# interface.net
KiCad netlist of a schematic drawn in EAGLE
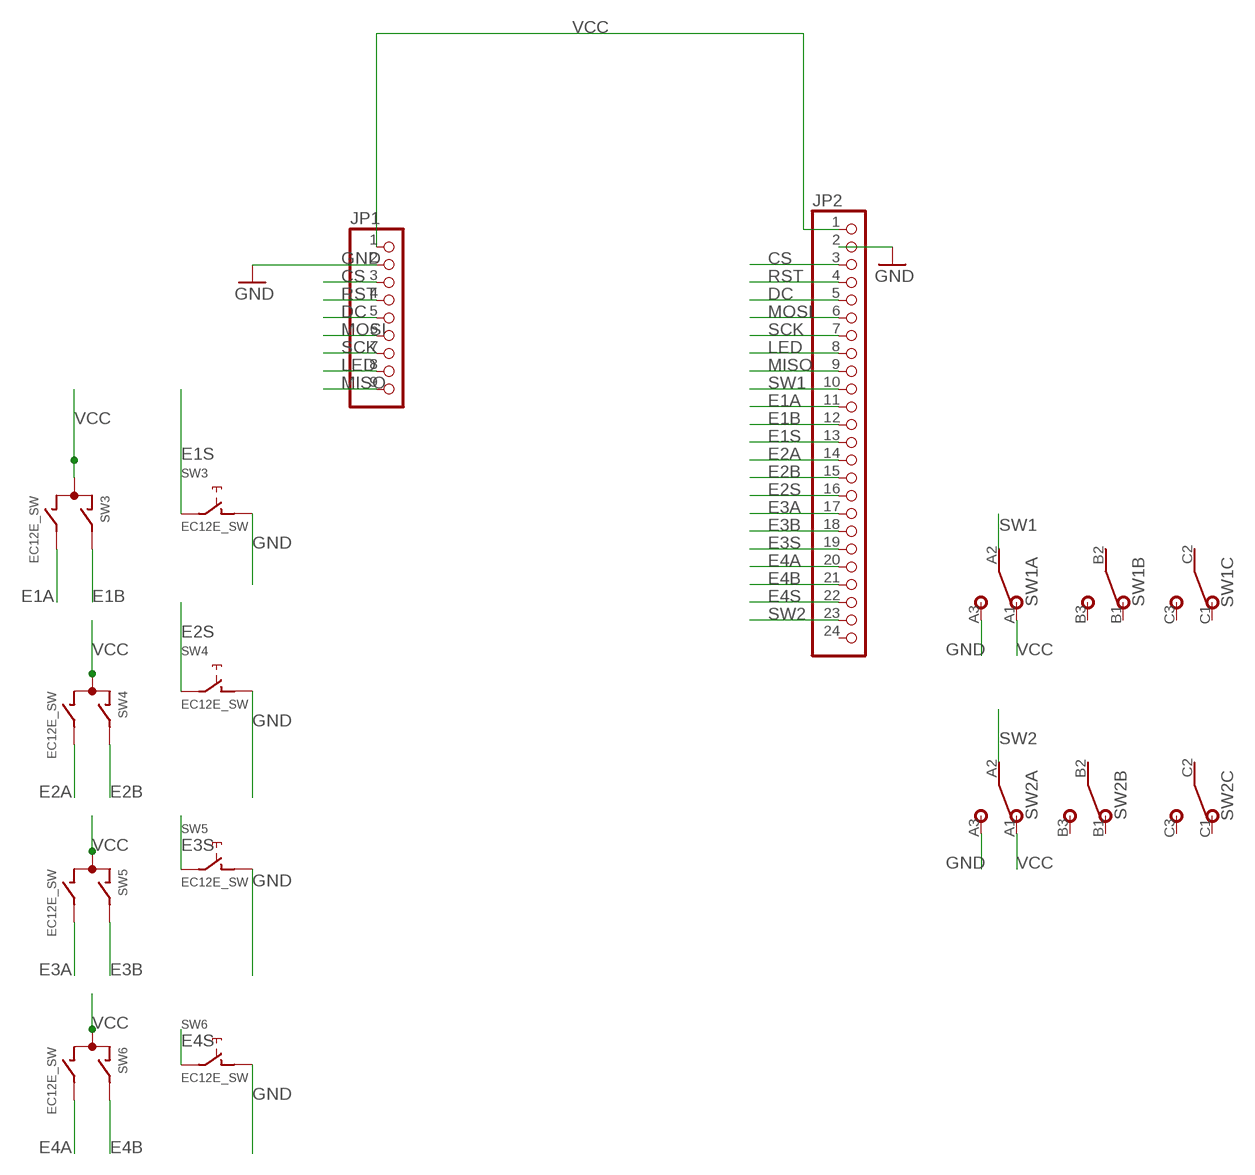
[diagram p0: schematic, sheet 1]

(export (version "E")
  (design (tool "Eeschema 10.0.6"))
  (components
    (comp (ref "JP1")
      (value "PINHD-1X9")
      (footprint "eagle-import:1X09")
      (libsource (lib "eagle-import") (part "PINHD-1X9"))
    )
    (comp (ref "JP2")
      (value "PINHD-1X24")
      (footprint "eagle-import:1X24")
      (libsource (lib "eagle-import") (part "PINHD-1X24"))
    )
    (comp (ref "SW1")
      (value "3PDTBLUE")
      (footprint "eagle-import:CHINABLUE")
      (libsource (lib "eagle-import") (part "3PDTBLUE"))
    )
    (comp (ref "SW2")
      (value "3PDTBLUE")
      (footprint "eagle-import:CHINABLUE")
      (libsource (lib "eagle-import") (part "3PDTBLUE"))
    )
    (comp (ref "SW3")
      (value "EC12E_SW")
      (footprint "eagle-import:ALPS_EC12E_SW")
      (fields (field (name "MPN") "EC12E2424407"))
      (libsource (lib "eagle-import") (part "EC12E_SW"))
    )
    (comp (ref "SW4")
      (value "EC12E_SW")
      (footprint "eagle-import:ALPS_EC12E_SW")
      (fields (field (name "MPN") "EC12E2424407"))
      (libsource (lib "eagle-import") (part "EC12E_SW"))
    )
    (comp (ref "SW5")
      (value "EC12E_SW")
      (footprint "eagle-import:ALPS_EC12E_SW")
      (fields (field (name "MPN") "EC12E2424407"))
      (libsource (lib "eagle-import") (part "EC12E_SW"))
    )
    (comp (ref "SW6")
      (value "EC12E_SW")
      (footprint "eagle-import:ALPS_EC12E_SW")
      (fields (field (name "MPN") "EC12E2424407"))
      (libsource (lib "eagle-import") (part "EC12E_SW"))
    )
  )
  (nets
    (net (code "1") (name "/CS") (class "Default")
      (node (ref "JP1") (pin "3") (pinfunction "3_3") (pintype "passive"))
      (node (ref "JP2") (pin "3") (pinfunction "3_3") (pintype "passive"))
    )
    (net (code "2") (name "/DC") (class "Default")
      (node (ref "JP1") (pin "5") (pinfunction "5_5") (pintype "passive"))
      (node (ref "JP2") (pin "5") (pinfunction "5_5") (pintype "passive"))
    )
    (net (code "3") (name "/E1A") (class "Default")
      (node (ref "JP2") (pin "11") (pinfunction "11_11") (pintype "passive"))
      (node (ref "SW3") (pin "B") (pinfunction "B_B") (pintype "passive"))
    )
    (net (code "4") (name "/E1B") (class "Default")
      (node (ref "JP2") (pin "12") (pinfunction "12_12") (pintype "passive"))
      (node (ref "SW3") (pin "A") (pinfunction "A_A") (pintype "passive"))
    )
    (net (code "5") (name "/E1S") (class "Default")
      (node (ref "JP2") (pin "13") (pinfunction "13_13") (pintype "passive"))
      (node (ref "SW3") (pin "E") (pinfunction "2_E") (pintype "passive"))
    )
    (net (code "6") (name "/E2A") (class "Default")
      (node (ref "JP2") (pin "14") (pinfunction "14_14") (pintype "passive"))
      (node (ref "SW4") (pin "B") (pinfunction "B_B") (pintype "passive"))
    )
    (net (code "7") (name "/E2B") (class "Default")
      (node (ref "JP2") (pin "15") (pinfunction "15_15") (pintype "passive"))
      (node (ref "SW4") (pin "A") (pinfunction "A_A") (pintype "passive"))
    )
    (net (code "8") (name "/E2S") (class "Default")
      (node (ref "JP2") (pin "16") (pinfunction "16_16") (pintype "passive"))
      (node (ref "SW4") (pin "E") (pinfunction "2_E") (pintype "passive"))
    )
    (net (code "9") (name "/E3A") (class "Default")
      (node (ref "JP2") (pin "17") (pinfunction "17_17") (pintype "passive"))
      (node (ref "SW5") (pin "B") (pinfunction "B_B") (pintype "passive"))
    )
    (net (code "10") (name "/E3B") (class "Default")
      (node (ref "JP2") (pin "18") (pinfunction "18_18") (pintype "passive"))
      (node (ref "SW5") (pin "A") (pinfunction "A_A") (pintype "passive"))
    )
    (net (code "11") (name "/E3S") (class "Default")
      (node (ref "JP2") (pin "19") (pinfunction "19_19") (pintype "passive"))
      (node (ref "SW5") (pin "E") (pinfunction "2_E") (pintype "passive"))
    )
    (net (code "12") (name "/E4A") (class "Default")
      (node (ref "JP2") (pin "20") (pinfunction "20_20") (pintype "passive"))
      (node (ref "SW6") (pin "B") (pinfunction "B_B") (pintype "passive"))
    )
    (net (code "13") (name "/E4B") (class "Default")
      (node (ref "JP2") (pin "21") (pinfunction "21_21") (pintype "passive"))
      (node (ref "SW6") (pin "A") (pinfunction "A_A") (pintype "passive"))
    )
    (net (code "14") (name "/E4S") (class "Default")
      (node (ref "JP2") (pin "22") (pinfunction "22_22") (pintype "passive"))
      (node (ref "SW6") (pin "E") (pinfunction "2_E") (pintype "passive"))
    )
    (net (code "15") (name "/LED") (class "Default")
      (node (ref "JP1") (pin "8") (pinfunction "8_8") (pintype "passive"))
      (node (ref "JP2") (pin "8") (pinfunction "8_8") (pintype "passive"))
    )
    (net (code "16") (name "/MISO") (class "Default")
      (node (ref "JP1") (pin "9") (pinfunction "9_9") (pintype "passive"))
      (node (ref "JP2") (pin "9") (pinfunction "9_9") (pintype "passive"))
    )
    (net (code "17") (name "/MOSI") (class "Default")
      (node (ref "JP1") (pin "6") (pinfunction "6_6") (pintype "passive"))
      (node (ref "JP2") (pin "6") (pinfunction "6_6") (pintype "passive"))
    )
    (net (code "18") (name "/RST") (class "Default")
      (node (ref "JP1") (pin "4") (pinfunction "4_4") (pintype "passive"))
      (node (ref "JP2") (pin "4") (pinfunction "4_4") (pintype "passive"))
    )
    (net (code "19") (name "/SCK") (class "Default")
      (node (ref "JP1") (pin "7") (pinfunction "7_7") (pintype "passive"))
      (node (ref "JP2") (pin "7") (pinfunction "7_7") (pintype "passive"))
    )
    (net (code "20") (name "/SW1") (class "Default")
      (node (ref "JP2") (pin "10") (pinfunction "10_10") (pintype "passive"))
      (node (ref "SW1") (pin "A2") (pinfunction "2_A2") (pintype "passive"))
    )
    (net (code "21") (name "/SW2") (class "Default")
      (node (ref "JP2") (pin "23") (pinfunction "23_23") (pintype "passive"))
      (node (ref "SW2") (pin "A2") (pinfunction "2_A2") (pintype "passive"))
    )
    (net (code "22") (name "/VCC") (class "Default")
      (node (ref "JP1") (pin "1") (pinfunction "1_1") (pintype "passive"))
      (node (ref "JP2") (pin "1") (pinfunction "1_1") (pintype "passive"))
      (node (ref "SW1") (pin "A1") (pinfunction "1_A1") (pintype "passive"))
      (node (ref "SW2") (pin "A1") (pinfunction "1_A1") (pintype "passive"))
      (node (ref "SW3") (pin "C") (pinfunction "C_C") (pintype "passive"))
      (node (ref "SW4") (pin "C") (pinfunction "C_C") (pintype "passive"))
      (node (ref "SW5") (pin "C") (pinfunction "C_C") (pintype "passive"))
      (node (ref "SW6") (pin "C") (pinfunction "C_C") (pintype "passive"))
    )
    (net (code "23") (name "GND") (class "Default")
      (node (ref "JP1") (pin "2") (pinfunction "2_2") (pintype "passive"))
      (node (ref "JP2") (pin "2") (pinfunction "2_2") (pintype "passive"))
      (node (ref "SW1") (pin "A3") (pinfunction "3_A3") (pintype "passive"))
      (node (ref "SW2") (pin "A3") (pinfunction "3_A3") (pintype "passive"))
      (node (ref "SW3") (pin "D") (pinfunction "1_D") (pintype "passive"))
      (node (ref "SW4") (pin "D") (pinfunction "1_D") (pintype "passive"))
      (node (ref "SW5") (pin "D") (pinfunction "1_D") (pintype "passive"))
      (node (ref "SW6") (pin "D") (pinfunction "1_D") (pintype "passive"))
    )
    (net (code "24") (name "unconnected-(JP2-Pad24)") (class "Default")
      (node (ref "JP2") (pin "24") (pinfunction "24_24") (pintype "passive"))
    )
    (net (code "25") (name "unconnected-(SW1B-1-PadB1)") (class "Default")
      (node (ref "SW1") (pin "B1") (pinfunction "1_B1") (pintype "passive"))
    )
    (net (code "26") (name "unconnected-(SW1B-2-PadB2)") (class "Default")
      (node (ref "SW1") (pin "B2") (pinfunction "2_B2") (pintype "passive"))
    )
    (net (code "27") (name "unconnected-(SW1B-3-PadB3)") (class "Default")
      (node (ref "SW1") (pin "B3") (pinfunction "3_B3") (pintype "passive"))
    )
    (net (code "28") (name "unconnected-(SW1C-1-PadC1)") (class "Default")
      (node (ref "SW1") (pin "C1") (pinfunction "1_C1") (pintype "passive"))
    )
    (net (code "29") (name "unconnected-(SW1C-2-PadC2)") (class "Default")
      (node (ref "SW1") (pin "C2") (pinfunction "2_C2") (pintype "passive"))
    )
    (net (code "30") (name "unconnected-(SW1C-3-PadC3)") (class "Default")
      (node (ref "SW1") (pin "C3") (pinfunction "3_C3") (pintype "passive"))
    )
    (net (code "31") (name "unconnected-(SW2B-1-PadB1)") (class "Default")
      (node (ref "SW2") (pin "B1") (pinfunction "1_B1") (pintype "passive"))
    )
    (net (code "32") (name "unconnected-(SW2B-2-PadB2)") (class "Default")
      (node (ref "SW2") (pin "B2") (pinfunction "2_B2") (pintype "passive"))
    )
    (net (code "33") (name "unconnected-(SW2B-3-PadB3)") (class "Default")
      (node (ref "SW2") (pin "B3") (pinfunction "3_B3") (pintype "passive"))
    )
    (net (code "34") (name "unconnected-(SW2C-1-PadC1)") (class "Default")
      (node (ref "SW2") (pin "C1") (pinfunction "1_C1") (pintype "passive"))
    )
    (net (code "35") (name "unconnected-(SW2C-2-PadC2)") (class "Default")
      (node (ref "SW2") (pin "C2") (pinfunction "2_C2") (pintype "passive"))
    )
    (net (code "36") (name "unconnected-(SW2C-3-PadC3)") (class "Default")
      (node (ref "SW2") (pin "C3") (pinfunction "3_C3") (pintype "passive"))
    )
  )
)
